# projekt_MIKRO.net
KiCad netlist of a schematic drawn in EAGLE
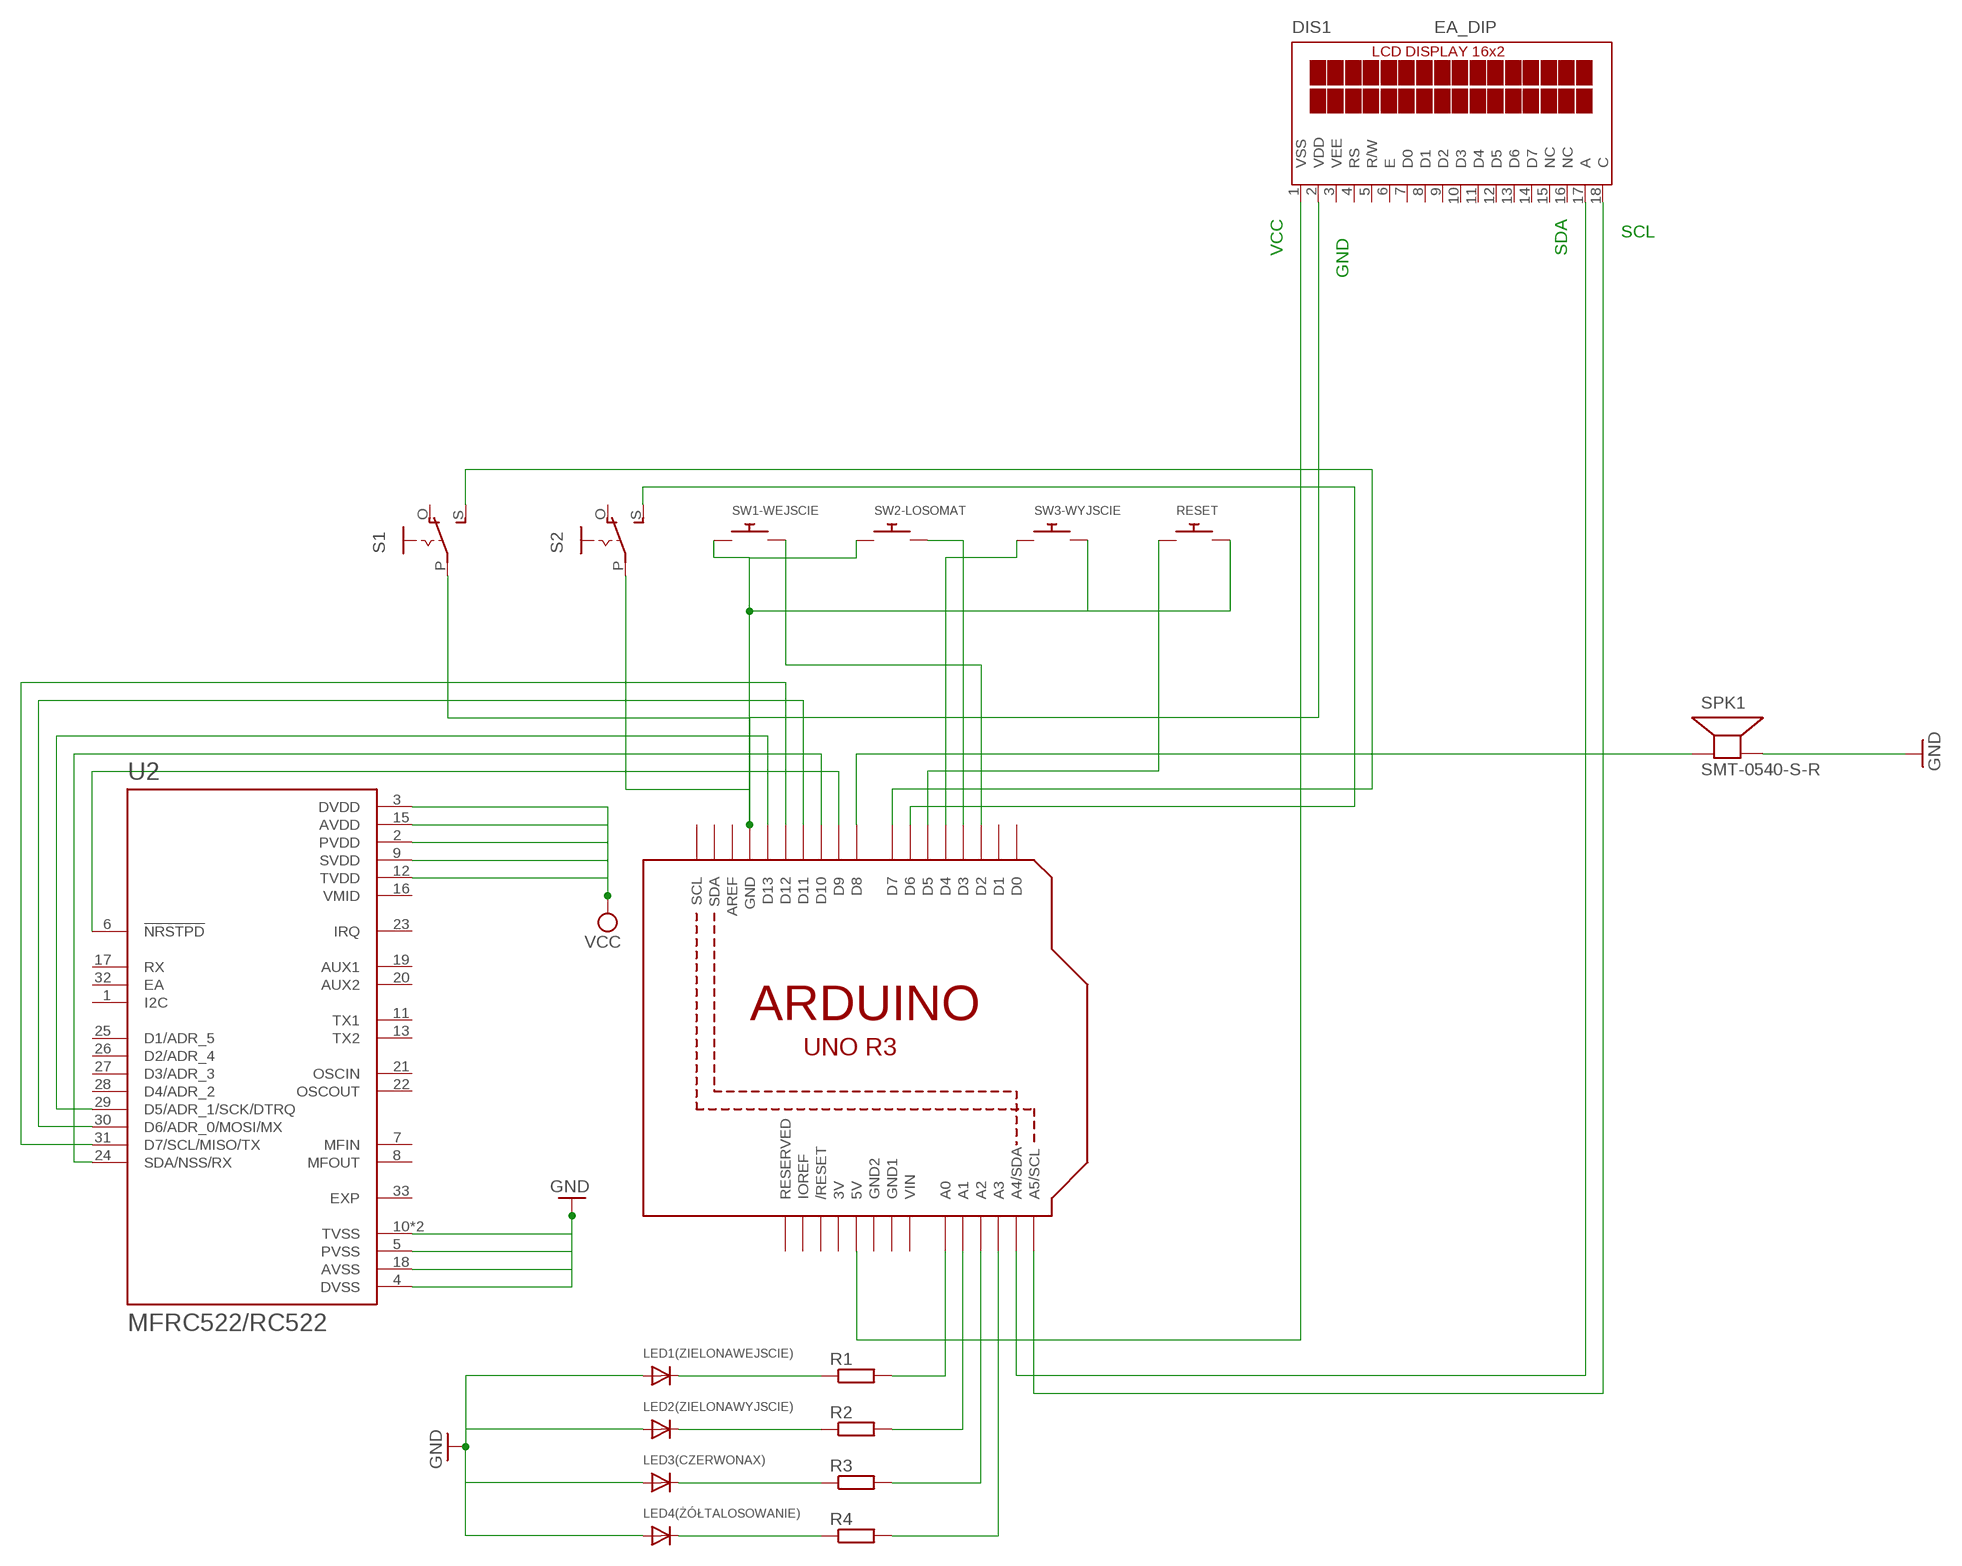
[diagram p0: schematic, sheet 1]

(export (version "E")
  (design (tool "Eeschema 10.0.6"))
  (components
    (comp (ref "DIS1")
      (value "EA_DIP")
      (footprint "eagle-import:EA_DIP")
      (libsource (lib "eagle-import") (part "EA_DIP"))
    )
    (comp (ref "LED1(ZIELONAWEJSCIE)")
      (value "DIODEDO-1N4148")
      (footprint "eagle-import:DO-1N4148")
      (libsource (lib "eagle-import") (part "DIODEDO-1N4148"))
    )
    (comp (ref "LED2(ZIELONAWYJSCIE)")
      (value "DIODEDO-1N4148")
      (footprint "eagle-import:DO-1N4148")
      (libsource (lib "eagle-import") (part "DIODEDO-1N4148"))
    )
    (comp (ref "LED3(CZERWONAX)")
      (value "DIODEDO-1N4148")
      (footprint "eagle-import:DO-1N4148")
      (libsource (lib "eagle-import") (part "DIODEDO-1N4148"))
    )
    (comp (ref "LED4(ŻÓŁTALOSOWANIE)")
      (value "DIODEDO-1N4148")
      (footprint "eagle-import:DO-1N4148")
      (libsource (lib "eagle-import") (part "DIODEDO-1N4148"))
    )
    (comp (ref "R1")
      (value "R-EU_VMTB60")
      (footprint "eagle-import:VMTB60")
      (libsource (lib "eagle-import") (part "R-EU_VMTB60"))
    )
    (comp (ref "R2")
      (value "R-EU_VMTB60")
      (footprint "eagle-import:VMTB60")
      (libsource (lib "eagle-import") (part "R-EU_VMTB60"))
    )
    (comp (ref "R3")
      (value "R-EU_VMTB60")
      (footprint "eagle-import:VMTB60")
      (libsource (lib "eagle-import") (part "R-EU_VMTB60"))
    )
    (comp (ref "R4")
      (value "R-EU_VMTB60")
      (footprint "eagle-import:VMTB60")
      (libsource (lib "eagle-import") (part "R-EU_VMTB60"))
    )
    (comp (ref "RESET")
      (value "SWITCH_PUSHBUTTONEVQ-PE")
      (footprint "eagle-import:TACT_PANA-EVQ")
      (libsource (lib "eagle-import") (part "SWITCH_PUSHBUTTONEVQ-PE"))
    )
    (comp (ref "S1")
      (value "EG1218S")
      (footprint "eagle-import:EG1218")
      (libsource (lib "eagle-import") (part "EG1218S"))
    )
    (comp (ref "S2")
      (value "EG1218S")
      (footprint "eagle-import:EG1218")
      (libsource (lib "eagle-import") (part "EG1218S"))
    )
    (comp (ref "SPK1")
      (value "SMT-0540-S-R")
      (footprint "eagle-import:SMT-0540-S-R")
      (libsource (lib "eagle-import") (part "SMT-0540-S-R"))
    )
    (comp (ref "SW1-WEJSCIE")
      (value "SWITCH_PUSHBUTTONEVQ-PE")
      (footprint "eagle-import:TACT_PANA-EVQ")
      (libsource (lib "eagle-import") (part "SWITCH_PUSHBUTTONEVQ-PE"))
    )
    (comp (ref "SW2-LOSOMAT")
      (value "SWITCH_PUSHBUTTONEVQ-PE")
      (footprint "eagle-import:TACT_PANA-EVQ")
      (libsource (lib "eagle-import") (part "SWITCH_PUSHBUTTONEVQ-PE"))
    )
    (comp (ref "SW3-WYJSCIE")
      (value "SWITCH_PUSHBUTTONEVQ-PE")
      (footprint "eagle-import:TACT_PANA-EVQ")
      (libsource (lib "eagle-import") (part "SWITCH_PUSHBUTTONEVQ-PE"))
    )
    (comp (ref "U1")
      (value "ARDUINOR3-DIMENSION")
      (footprint "eagle-import:ARDUINOR3")
      (libsource (lib "eagle-import") (part "ARDUINOR3-DIMENSION"))
    )
    (comp (ref "U2")
      (value "MFRC522/RC522")
      (footprint "eagle-import:QFN50P500X500X100-33N")
      (fields (field (name "MF") "NXP Semiconductors"))
      (libsource (lib "eagle-import") (part "MFRC522/RC522"))
    )
  )
  (nets
    (net (code "1") (name "/3V") (class "Default")
      (node (ref "U1") (pin "3V") (pinfunction "3V_3V") (pintype "power_in"))
    )
    (net (code "2") (name "/GND1") (class "Default")
      (node (ref "U1") (pin "GND1") (pinfunction "GND1_GND1") (pintype "power_in"))
    )
    (net (code "3") (name "/GND2") (class "Default")
      (node (ref "U1") (pin "GND2") (pinfunction "GND2_GND2") (pintype "power_in"))
    )
    (net (code "4") (name "/VEE") (class "Default")
      (node (ref "DIS1") (pin "3") (pinfunction "VEE_3") (pintype "power_in"))
    )
    (net (code "5") (name "/VIN") (class "Default")
      (node (ref "U1") (pin "VIN") (pinfunction "VIN_VIN") (pintype "power_in"))
    )
    (net (code "6") (name "/VMID") (class "Default")
      (node (ref "U2") (pin "16") (pinfunction "VMID_16") (pintype "power_in"))
    )
    (net (code "7") (name "GND") (class "Default")
      (node (ref "LED1(ZIELONAWEJSCIE)") (pin "A") (pinfunction "A_A") (pintype "passive"))
      (node (ref "LED2(ZIELONAWYJSCIE)") (pin "A") (pinfunction "A_A") (pintype "passive"))
      (node (ref "LED3(CZERWONAX)") (pin "A") (pinfunction "A_A") (pintype "passive"))
      (node (ref "LED4(ŻÓŁTALOSOWANIE)") (pin "A") (pinfunction "A_A") (pintype "passive"))
      (node (ref "SPK1") (pin "+") (pinfunction "-_+") (pintype "passive"))
      (node (ref "U2") (pin "10") (pinfunction "TVSS_10") (pintype "power_in"))
      (node (ref "U2") (pin "14") (pinfunction "TVSS_14") (pintype "power_in"))
      (node (ref "U2") (pin "18") (pinfunction "AVSS_18") (pintype "power_in"))
      (node (ref "U2") (pin "4") (pinfunction "DVSS_4") (pintype "power_in"))
      (node (ref "U2") (pin "5") (pinfunction "PVSS_5") (pintype "power_in"))
    )
    (net (code "8") (name "Net-(DIS1-A)") (class "Default")
      (node (ref "DIS1") (pin "17") (pinfunction "A_17") (pintype "passive"))
      (node (ref "U1") (pin "A4") (pinfunction "A4/SDA_A4") (pintype "bidirectional"))
    )
    (net (code "9") (name "Net-(DIS1-C)") (class "Default")
      (node (ref "DIS1") (pin "18") (pinfunction "C_18") (pintype "passive"))
      (node (ref "U1") (pin "A5") (pinfunction "A5/SCL_A5") (pintype "bidirectional"))
    )
    (net (code "10") (name "Net-(DIS1-VDD)") (class "Default")
      (node (ref "DIS1") (pin "2") (pinfunction "VDD_2") (pintype "power_in"))
      (node (ref "RESET") (pin "P$2") (pinfunction "P$2_P$2") (pintype "passive"))
      (node (ref "S1") (pin "P") (pinfunction "P_P") (pintype "passive"))
      (node (ref "S2") (pin "P") (pinfunction "P_P") (pintype "passive"))
      (node (ref "SW1-WEJSCIE") (pin "P$1") (pinfunction "P$1_P$1") (pintype "passive"))
      (node (ref "SW2-LOSOMAT") (pin "P$1") (pinfunction "P$1_P$1") (pintype "passive"))
      (node (ref "SW3-WYJSCIE") (pin "P$2") (pinfunction "P$2_P$2") (pintype "passive"))
      (node (ref "U1") (pin "GND") (pinfunction "GND_GND") (pintype "power_in"))
    )
    (net (code "11") (name "Net-(DIS1-VSS)") (class "Default")
      (node (ref "DIS1") (pin "1") (pinfunction "VSS_1") (pintype "power_in"))
      (node (ref "U1") (pin "5V") (pinfunction "5V_5V") (pintype "power_in"))
    )
    (net (code "12") (name "Net-(LED1(ZIELONAWEJSCIE)-PadC)") (class "Default")
      (node (ref "LED1(ZIELONAWEJSCIE)") (pin "C") (pinfunction "C_C") (pintype "passive"))
      (node (ref "R1") (pin "1") (pinfunction "1_1") (pintype "passive"))
    )
    (net (code "13") (name "Net-(LED2(ZIELONAWYJSCIE)-PadC)") (class "Default")
      (node (ref "LED2(ZIELONAWYJSCIE)") (pin "C") (pinfunction "C_C") (pintype "passive"))
      (node (ref "R2") (pin "1") (pinfunction "1_1") (pintype "passive"))
    )
    (net (code "14") (name "Net-(LED3(CZERWONAX)-PadC)") (class "Default")
      (node (ref "LED3(CZERWONAX)") (pin "C") (pinfunction "C_C") (pintype "passive"))
      (node (ref "R3") (pin "1") (pinfunction "1_1") (pintype "passive"))
    )
    (net (code "15") (name "Net-(LED4(ŻÓŁTALOSOWANIE)-PadC)") (class "Default")
      (node (ref "LED4(ŻÓŁTALOSOWANIE)") (pin "C") (pinfunction "C_C") (pintype "passive"))
      (node (ref "R4") (pin "1") (pinfunction "1_1") (pintype "passive"))
    )
    (net (code "16") (name "Net-(R1-Pad2)") (class "Default")
      (node (ref "R1") (pin "2") (pinfunction "2_2") (pintype "passive"))
      (node (ref "U1") (pin "A0") (pinfunction "A0_A0") (pintype "bidirectional"))
    )
    (net (code "17") (name "Net-(R2-Pad2)") (class "Default")
      (node (ref "R2") (pin "2") (pinfunction "2_2") (pintype "passive"))
      (node (ref "U1") (pin "A1") (pinfunction "A1_A1") (pintype "bidirectional"))
    )
    (net (code "18") (name "Net-(R3-Pad2)") (class "Default")
      (node (ref "R3") (pin "2") (pinfunction "2_2") (pintype "passive"))
      (node (ref "U1") (pin "A2") (pinfunction "A2_A2") (pintype "bidirectional"))
    )
    (net (code "19") (name "Net-(R4-Pad2)") (class "Default")
      (node (ref "R4") (pin "2") (pinfunction "2_2") (pintype "passive"))
      (node (ref "U1") (pin "A3") (pinfunction "A3_A3") (pintype "bidirectional"))
    )
    (net (code "20") (name "Net-(RESET-PadP$1)") (class "Default")
      (node (ref "RESET") (pin "P$1") (pinfunction "P$1_P$1") (pintype "passive"))
      (node (ref "U1") (pin "D5") (pinfunction "D5_D5") (pintype "bidirectional"))
    )
    (net (code "21") (name "Net-(S1-PadS)") (class "Default")
      (node (ref "S1") (pin "S") (pinfunction "S_S") (pintype "passive"))
      (node (ref "U1") (pin "D7") (pinfunction "D7_D7") (pintype "bidirectional"))
    )
    (net (code "22") (name "Net-(S2-PadS)") (class "Default")
      (node (ref "S2") (pin "S") (pinfunction "S_S") (pintype "passive"))
      (node (ref "U1") (pin "D6") (pinfunction "D6_D6") (pintype "bidirectional"))
    )
    (net (code "23") (name "Net-(SPK1-+)") (class "Default")
      (node (ref "SPK1") (pin "-") (pinfunction "+_-") (pintype "passive"))
      (node (ref "U1") (pin "D8") (pinfunction "D8_D8") (pintype "bidirectional"))
    )
    (net (code "24") (name "Net-(SW1-WEJSCIE-PadP$2)") (class "Default")
      (node (ref "SW1-WEJSCIE") (pin "P$2") (pinfunction "P$2_P$2") (pintype "passive"))
      (node (ref "U1") (pin "D2") (pinfunction "D2_D2") (pintype "bidirectional"))
    )
    (net (code "25") (name "Net-(SW2-LOSOMAT-PadP$2)") (class "Default")
      (node (ref "SW2-LOSOMAT") (pin "P$2") (pinfunction "P$2_P$2") (pintype "passive"))
      (node (ref "U1") (pin "D3") (pinfunction "D3_D3") (pintype "bidirectional"))
    )
    (net (code "26") (name "Net-(SW3-WYJSCIE-PadP$1)") (class "Default")
      (node (ref "SW3-WYJSCIE") (pin "P$1") (pinfunction "P$1_P$1") (pintype "passive"))
      (node (ref "U1") (pin "D4") (pinfunction "D4_D4") (pintype "bidirectional"))
    )
    (net (code "27") (name "Net-(U2-D5{slash}ADR_1{slash}SCK{slash}DTRQ)") (class "Default")
      (node (ref "U1") (pin "D13") (pinfunction "D13_D13") (pintype "bidirectional"))
      (node (ref "U2") (pin "29") (pinfunction "D5/ADR_1/SCK/DTRQ_29") (pintype "bidirectional"))
    )
    (net (code "28") (name "Net-(U2-D6{slash}ADR_0{slash}MOSI{slash}MX)") (class "Default")
      (node (ref "U1") (pin "D11") (pinfunction "D11_D11") (pintype "bidirectional"))
      (node (ref "U2") (pin "30") (pinfunction "D6/ADR_0/MOSI/MX_30") (pintype "bidirectional"))
    )
    (net (code "29") (name "Net-(U2-D7{slash}SCL{slash}MISO{slash}TX)") (class "Default")
      (node (ref "U1") (pin "D12") (pinfunction "D12_D12") (pintype "bidirectional"))
      (node (ref "U2") (pin "31") (pinfunction "D7/SCL/MISO/TX_31") (pintype "bidirectional"))
    )
    (net (code "30") (name "Net-(U2-SDA{slash}NSS{slash}RX)") (class "Default")
      (node (ref "U1") (pin "D10") (pinfunction "D10_D10") (pintype "bidirectional"))
      (node (ref "U2") (pin "24") (pinfunction "SDA/NSS/RX_24") (pintype "bidirectional"))
    )
    (net (code "31") (name "Net-(U2-~{NRSTPD})") (class "Default")
      (node (ref "U1") (pin "D9") (pinfunction "D9_D9") (pintype "bidirectional"))
      (node (ref "U2") (pin "6") (pinfunction "~{NRSTPD}_6") (pintype "input"))
    )
    (net (code "32") (name "VCC") (class "Default")
      (node (ref "U2") (pin "12") (pinfunction "TVDD_12") (pintype "power_in"))
      (node (ref "U2") (pin "15") (pinfunction "AVDD_15") (pintype "power_in"))
      (node (ref "U2") (pin "2") (pinfunction "PVDD_2") (pintype "power_in"))
      (node (ref "U2") (pin "3") (pinfunction "DVDD_3") (pintype "power_in"))
      (node (ref "U2") (pin "9") (pinfunction "SVDD_9") (pintype "power_in"))
    )
    (net (code "33") (name "unconnected-(DIS1-D0-Pad7)") (class "Default")
      (node (ref "DIS1") (pin "7") (pinfunction "D0_7") (pintype "input"))
    )
    (net (code "34") (name "unconnected-(DIS1-D1-Pad8)") (class "Default")
      (node (ref "DIS1") (pin "8") (pinfunction "D1_8") (pintype "input"))
    )
    (net (code "35") (name "unconnected-(DIS1-D2-Pad9)") (class "Default")
      (node (ref "DIS1") (pin "9") (pinfunction "D2_9") (pintype "input"))
    )
    (net (code "36") (name "unconnected-(DIS1-D3-Pad10)") (class "Default")
      (node (ref "DIS1") (pin "10") (pinfunction "D3_10") (pintype "input"))
    )
    (net (code "37") (name "unconnected-(DIS1-D4-Pad11)") (class "Default")
      (node (ref "DIS1") (pin "11") (pinfunction "D4_11") (pintype "input"))
    )
    (net (code "38") (name "unconnected-(DIS1-D5-Pad12)") (class "Default")
      (node (ref "DIS1") (pin "12") (pinfunction "D5_12") (pintype "input"))
    )
    (net (code "39") (name "unconnected-(DIS1-D6-Pad13)") (class "Default")
      (node (ref "DIS1") (pin "13") (pinfunction "D6_13") (pintype "input"))
    )
    (net (code "40") (name "unconnected-(DIS1-D7-Pad14)") (class "Default")
      (node (ref "DIS1") (pin "14") (pinfunction "D7_14") (pintype "input"))
    )
    (net (code "41") (name "unconnected-(DIS1-E-Pad6)") (class "Default")
      (node (ref "DIS1") (pin "6") (pinfunction "E_6") (pintype "input"))
    )
    (net (code "42") (name "unconnected-(DIS1-NC-Pad15)") (class "Default")
      (node (ref "DIS1") (pin "15") (pinfunction "NC_15") (pintype "no_connect"))
    )
    (net (code "43") (name "unconnected-(DIS1-NC-Pad16)") (class "Default")
      (node (ref "DIS1") (pin "16") (pinfunction "NC_16") (pintype "no_connect"))
    )
    (net (code "44") (name "unconnected-(DIS1-RS-Pad4)") (class "Default")
      (node (ref "DIS1") (pin "4") (pinfunction "RS_4") (pintype "input"))
    )
    (net (code "45") (name "unconnected-(DIS1-R{slash}W-Pad5)") (class "Default")
      (node (ref "DIS1") (pin "5") (pinfunction "R/W_5") (pintype "input"))
    )
    (net (code "46") (name "unconnected-(S1-PadO)") (class "Default")
      (node (ref "S1") (pin "O") (pinfunction "O_O") (pintype "passive"))
    )
    (net (code "47") (name "unconnected-(S2-PadO)") (class "Default")
      (node (ref "S2") (pin "O") (pinfunction "O_O") (pintype "passive"))
    )
    (net (code "48") (name "unconnected-(U1-PadAREF)") (class "Default")
      (node (ref "U1") (pin "AREF") (pinfunction "AREF_AREF") (pintype "bidirectional"))
    )
    (net (code "49") (name "unconnected-(U1-PadD0)") (class "Default")
      (node (ref "U1") (pin "D0") (pinfunction "D0_D0") (pintype "bidirectional"))
    )
    (net (code "50") (name "unconnected-(U1-PadD1)") (class "Default")
      (node (ref "U1") (pin "D1") (pinfunction "D1_D1") (pintype "bidirectional"))
    )
    (net (code "51") (name "unconnected-(U1-PadIOREF)") (class "Default")
      (node (ref "U1") (pin "IOREF") (pinfunction "IOREF_IOREF") (pintype "output"))
    )
    (net (code "52") (name "unconnected-(U1-PadRESERVED)") (class "Default")
      (node (ref "U1") (pin "RESERVED") (pinfunction "RESERVED_RESERVED") (pintype "no_connect"))
    )
    (net (code "53") (name "unconnected-(U1-PadSCL)") (class "Default")
      (node (ref "U1") (pin "SCL") (pinfunction "SCL_SCL") (pintype "bidirectional"))
    )
    (net (code "54") (name "unconnected-(U1-PadSDA)") (class "Default")
      (node (ref "U1") (pin "SDA") (pinfunction "SDA_SDA") (pintype "bidirectional"))
    )
    (net (code "55") (name "unconnected-(U1-{slash}RESET-PadRESET)") (class "Default")
      (node (ref "U1") (pin "RESET") (pinfunction "/RESET_RESET") (pintype "bidirectional"))
    )
    (net (code "56") (name "unconnected-(U2-AUX1-Pad19)") (class "Default")
      (node (ref "U2") (pin "19") (pinfunction "AUX1_19") (pintype "output"))
    )
    (net (code "57") (name "unconnected-(U2-AUX2-Pad20)") (class "Default")
      (node (ref "U2") (pin "20") (pinfunction "AUX2_20") (pintype "output"))
    )
    (net (code "58") (name "unconnected-(U2-D1{slash}ADR_5-Pad25)") (class "Default")
      (node (ref "U2") (pin "25") (pinfunction "D1/ADR_5_25") (pintype "bidirectional"))
    )
    (net (code "59") (name "unconnected-(U2-D2{slash}ADR_4-Pad26)") (class "Default")
      (node (ref "U2") (pin "26") (pinfunction "D2/ADR_4_26") (pintype "bidirectional"))
    )
    (net (code "60") (name "unconnected-(U2-D3{slash}ADR_3-Pad27)") (class "Default")
      (node (ref "U2") (pin "27") (pinfunction "D3/ADR_3_27") (pintype "bidirectional"))
    )
    (net (code "61") (name "unconnected-(U2-D4{slash}ADR_2-Pad28)") (class "Default")
      (node (ref "U2") (pin "28") (pinfunction "D4/ADR_2_28") (pintype "bidirectional"))
    )
    (net (code "62") (name "unconnected-(U2-EA-Pad32)") (class "Default")
      (node (ref "U2") (pin "32") (pinfunction "EA_32") (pintype "input"))
    )
    (net (code "63") (name "unconnected-(U2-EXP-Pad33)") (class "Default")
      (node (ref "U2") (pin "33") (pinfunction "EXP_33") (pintype "passive"))
    )
    (net (code "64") (name "unconnected-(U2-I2C-Pad1)") (class "Default")
      (node (ref "U2") (pin "1") (pinfunction "I2C_1") (pintype "input"))
    )
    (net (code "65") (name "unconnected-(U2-IRQ-Pad23)") (class "Default")
      (node (ref "U2") (pin "23") (pinfunction "IRQ_23") (pintype "output"))
    )
    (net (code "66") (name "unconnected-(U2-MFIN-Pad7)") (class "Default")
      (node (ref "U2") (pin "7") (pinfunction "MFIN_7") (pintype "input"))
    )
    (net (code "67") (name "unconnected-(U2-MFOUT-Pad8)") (class "Default")
      (node (ref "U2") (pin "8") (pinfunction "MFOUT_8") (pintype "output"))
    )
    (net (code "68") (name "unconnected-(U2-OSCIN-Pad21)") (class "Default")
      (node (ref "U2") (pin "21") (pinfunction "OSCIN_21") (pintype "input"))
    )
    (net (code "69") (name "unconnected-(U2-OSCOUT-Pad22)") (class "Default")
      (node (ref "U2") (pin "22") (pinfunction "OSCOUT_22") (pintype "output"))
    )
    (net (code "70") (name "unconnected-(U2-RX-Pad17)") (class "Default")
      (node (ref "U2") (pin "17") (pinfunction "RX_17") (pintype "input"))
    )
    (net (code "71") (name "unconnected-(U2-TX1-Pad11)") (class "Default")
      (node (ref "U2") (pin "11") (pinfunction "TX1_11") (pintype "output"))
    )
    (net (code "72") (name "unconnected-(U2-TX2-Pad13)") (class "Default")
      (node (ref "U2") (pin "13") (pinfunction "TX2_13") (pintype "output"))
    )
  )
)
